# W5500_HR911105A.net
KiCad netlist of a schematic drawn in Altium Designer
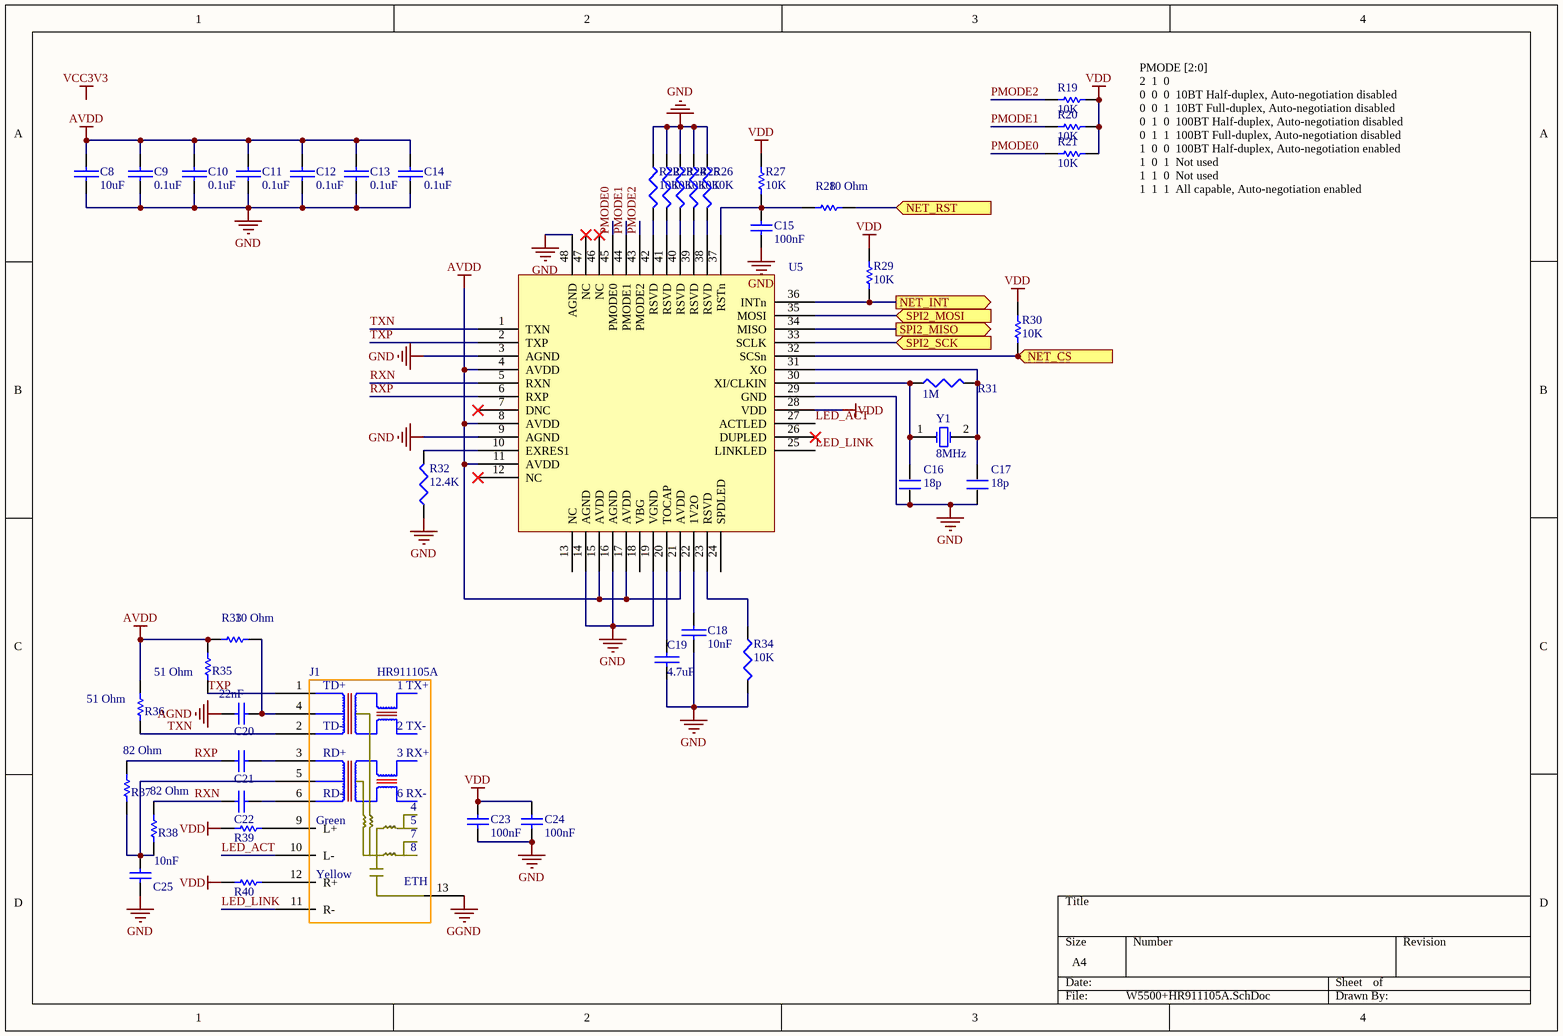
[diagram p0: W5500+HR911105A.SchDoc]

(export (version "E")
  (design (tool "Eeschema 10.0.6"))
  (components
    (comp (ref "C8")
      (value "10uF")
      (footprint "0805")
      (description "0.1uF")
      (libsource (lib "INSPUR_SCH") (part "CAP"))
    )
    (comp (ref "C9") (value "0.1uF") (footprint "0603") (libsource (lib "INSPUR_SCH") (part "CAP")))
    (comp (ref "C10") (value "0.1uF") (footprint "0603") (libsource (lib "INSPUR_SCH") (part "CAP")))
    (comp (ref "C11") (value "0.1uF") (footprint "0603") (libsource (lib "INSPUR_SCH") (part "CAP")))
    (comp (ref "C12") (value "0.1uF") (footprint "0603") (libsource (lib "INSPUR_SCH") (part "CAP")))
    (comp (ref "C13") (value "0.1uF") (footprint "0603") (libsource (lib "INSPUR_SCH") (part "CAP")))
    (comp (ref "C14") (value "0.1uF") (footprint "0603") (libsource (lib "INSPUR_SCH") (part "CAP")))
    (comp (ref "C15")
      (value "100nF")
      (footprint "CAPC0805(2012)145_N")
      (description "CAP 100nF 50V ±5% 0805 (2012 Metric) Thickness 1.45mm SMD")
      (fields (field (name "TOLERANCE") "±5%") (field (name "Comment") "CAP 100nF 50V 0805(2012)"))
      (libsource (lib "Altium Content Vault") (part "CMP-1036-04417-1"))
    )
    (comp (ref "C16") (value "18p") (footprint "0603") (libsource (lib "mylib") (part "C")))
    (comp (ref "C17") (value "18p") (footprint "0603") (libsource (lib "mylib") (part "C")))
    (comp (ref "C18") (value "10nF") (footprint "0603") (libsource (lib "INSPUR_SCH") (part "CAP")))
    (comp (ref "C19")
      (value "4.7uF")
      (footprint "0603")
      (description "0.1uF")
      (libsource (lib "INSPUR_SCH") (part "CAP"))
    )
    (comp (ref "C20")
      (value "22nF")
      (footprint "CAPC0805(2012)130_N")
      (description "CAP 22nF 50V ±5% 0805 (2012 Metric) Thickness 1.2mm SMD")
      (fields (field (name "TOLERANCE") "±5%") (field (name "Comment") "CAP 22nF 50V 0805(2012)"))
      (libsource (lib "Altium Content Vault") (part "CMP-1036-04061-1"))
    )
    (comp (ref "C21")
      (value "CAP 6.8nF 50V 0805(2012)")
      (footprint "CAPC0805(2012)100_L")
      (description "CAP 6.8nF 50V ±1% 0805 (2012 Metric) Thickness 1mm SMD")
      (fields (field (name "TOLERANCE") "±1%"))
      (libsource (lib "Altium Content Vault") (part "CAP"))
    )
    (comp (ref "C22")
      (value "CAP 6.8nF 50V 0805(2012)")
      (footprint "CAPC0805(2012)100_L")
      (description "CAP 6.8nF 50V ±1% 0805 (2012 Metric) Thickness 1mm SMD")
      (fields (field (name "TOLERANCE") "±1%"))
      (libsource (lib "Altium Content Vault") (part "CAP"))
    )
    (comp (ref "C23")
      (value "100nF")
      (footprint "CAPC0805(2012)100_L")
      (description "CAP 100nF 50V ±5% 0805 (2012 Metric) Thickness 1mm SMD")
      (fields (field (name "TOLERANCE") "±5%") (field (name "Comment") "CAP 100nF 50V 0805(2012)"))
      (libsource (lib "Altium Content Vault") (part "CMP-1036-04418-1"))
    )
    (comp (ref "C24")
      (value "100nF")
      (footprint "CAPC0805(2012)100_L")
      (description "CAP 100nF 50V ±5% 0805 (2012 Metric) Thickness 1mm SMD")
      (fields (field (name "TOLERANCE") "±5%") (field (name "Comment") "CAP 100nF 50V 0805(2012)"))
      (libsource (lib "Altium Content Vault") (part "CMP-1036-04418-1"))
    )
    (comp (ref "C25")
      (value "10nF")
      (footprint "CAPC0805(2012)100_M")
      (description "CAP 10nF 50V ±1% 0805 (2012 Metric) Thickness 1mm SMD")
      (fields (field (name "TOLERANCE") "±1%") (field (name "Comment") "CAP 10nF 50V 0805(2012)"))
      (libsource (lib "Altium Content Vault") (part "CMP-1036-03837-1"))
    )
    (comp (ref "J1") (value "HR911105A") (footprint "HR911102") (libsource (lib "*") (part "HR911102")))
    (comp (ref "R19")
      (value "10K")
      (footprint "RESC0805(2012)_M")
      (description "10K 0.125W 1% 0805 (2012 Metric)  SMD")
      (fields (field (name "TOLERANCE") "1 %") (field (name "POWER") "0.125 W"))
      (libsource (lib "Altium Content Vault") (part "CMP-1013-00623-1"))
    )
    (comp (ref "R20")
      (value "10K")
      (footprint "RESC0805(2012)_M")
      (description "10K 0.125W 1% 0805 (2012 Metric)  SMD")
      (fields (field (name "TOLERANCE") "1 %") (field (name "POWER") "0.125 W"))
      (libsource (lib "Altium Content Vault") (part "CMP-1013-00623-1"))
    )
    (comp (ref "R21")
      (value "10K")
      (footprint "RESC0805(2012)_M")
      (description "10K 0.125W 1% 0805 (2012 Metric)  SMD")
      (fields (field (name "TOLERANCE") "1 %") (field (name "POWER") "0.125 W"))
      (libsource (lib "Altium Content Vault") (part "CMP-1013-00623-1"))
    )
    (comp (ref "R22") (value "10K") (footprint "0603") (libsource (lib "INSPUR_SCH") (part "RES1")))
    (comp (ref "R23") (value "10K") (footprint "0603") (libsource (lib "INSPUR_SCH") (part "RES1")))
    (comp (ref "R24") (value "10K") (footprint "0603") (libsource (lib "INSPUR_SCH") (part "RES1")))
    (comp (ref "R25") (value "10K") (footprint "0603") (libsource (lib "INSPUR_SCH") (part "RES1")))
    (comp (ref "R26") (value "10K") (footprint "0603") (libsource (lib "INSPUR_SCH") (part "RES1")))
    (comp (ref "R27")
      (value "10K")
      (footprint "RESC0805(2012)_M")
      (description "10K 0.125W 1% 0805 (2012 Metric)  SMD")
      (fields (field (name "TOLERANCE") "1 %") (field (name "POWER") "0.125 W"))
      (libsource (lib "Altium Content Vault") (part "CMP-1013-00623-1"))
    )
    (comp (ref "R28")
      (value "10 Ohm")
      (footprint "RESC0805(2012)_L")
      (description "10R 0.125W 5% 0805 (2012 Metric)  SMD")
      (fields (field (name "POWER") "0.125 W") (field (name "TOLERANCE") "5 %"))
      (libsource (lib "Altium Content Vault") (part "CMP-1013-00026-1"))
    )
    (comp (ref "R29")
      (value "10K")
      (footprint "RESC0805(2012)_M")
      (description "10K 0.125W 1% 0805 (2012 Metric)  SMD")
      (fields (field (name "TOLERANCE") "1 %") (field (name "POWER") "0.125 W"))
      (libsource (lib "Altium Content Vault") (part "CMP-1013-00623-1"))
    )
    (comp (ref "R30")
      (value "10K")
      (footprint "RESC0805(2012)_M")
      (description "10K 0.125W 1% 0805 (2012 Metric)  SMD")
      (fields (field (name "TOLERANCE") "1 %") (field (name "POWER") "0.125 W"))
      (libsource (lib "Altium Content Vault") (part "CMP-1013-00623-1"))
    )
    (comp (ref "R31") (value "1M") (footprint "0603") (libsource (lib "INSPUR_SCH") (part "RES1")))
    (comp (ref "R32") (value "12.4K") (footprint "0603") (libsource (lib "INSPUR_SCH") (part "RES1")))
    (comp (ref "R33")
      (value "10 Ohm")
      (footprint "RESC0805(2012)_L")
      (description "10R 0.125W 5% 0805 (2012 Metric)  SMD")
      (fields (field (name "POWER") "0.125 W") (field (name "TOLERANCE") "5 %"))
      (libsource (lib "Altium Content Vault") (part "CMP-1013-00026-1"))
    )
    (comp (ref "R34") (value "10K") (footprint "0603") (libsource (lib "INSPUR_SCH") (part "RES1")))
    (comp (ref "R35")
      (value "51 Ohm")
      (footprint "RESC0805(2012)_N")
      (description "51R 0.125W 5% 0805 (2012 Metric)  SMD")
      (fields (field (name "TOLERANCE") "5 %") (field (name "POWER") "0.125 W"))
      (libsource (lib "Altium Content Vault") (part "CMP-1013-00043-1"))
    )
    (comp (ref "R36")
      (value "51 Ohm")
      (footprint "RESC0805(2012)_N")
      (description "51R 0.125W 5% 0805 (2012 Metric)  SMD")
      (fields (field (name "TOLERANCE") "5 %") (field (name "POWER") "0.125 W"))
      (libsource (lib "Altium Content Vault") (part "CMP-1013-00043-1"))
    )
    (comp (ref "R37")
      (value "82 Ohm")
      (footprint "RESC0805(2012)_L")
      (description "82R 0.125W 5% 0805 (2012 Metric)  SMD")
      (fields (field (name "POWER") "0.125 W") (field (name "TOLERANCE") "5 %"))
      (libsource (lib "Altium Content Vault") (part "CMP-1013-00048-1"))
    )
    (comp (ref "R38")
      (value "82 Ohm")
      (footprint "RESC0805(2012)_L")
      (description "82R 0.125W 5% 0805 (2012 Metric)  SMD")
      (fields (field (name "POWER") "0.125 W") (field (name "TOLERANCE") "5 %"))
      (libsource (lib "Altium Content Vault") (part "CMP-1013-00048-1"))
    )
    (comp (ref "R39")
      (value "270R 5% 0805(2012)")
      (footprint "RESC0805(2012)_N")
      (description "270R 0.125W 5% 0805 (2012 Metric)  SMD")
      (fields (field (name "POWER") "0.125 W") (field (name "TOLERANCE") "5 %"))
      (libsource (lib "Altium Content Vault") (part "RES"))
    )
    (comp (ref "R40")
      (value "270R 5% 0805(2012)")
      (footprint "RESC0805(2012)_N")
      (description "270R 0.125W 5% 0805 (2012 Metric)  SMD")
      (fields (field (name "POWER") "0.125 W") (field (name "TOLERANCE") "5 %"))
      (libsource (lib "Altium Content Vault") (part "RES"))
    )
    (comp (ref "U5")
      (value "W5500")
      (footprint "LQFP48_N")
      (description "以太网")
      (libsource (lib "mylib") (part "W5500"))
    )
    (comp (ref "Y1")
      (value "8MHz")
      (footprint "XTAL_US")
      (description "Crystal Oscillator")
      (fields (field (name "PUBLISHER") "Altium Limited"))
      (libsource (lib "mylib") (part "XTAL"))
    )
  )
  (nets
    (net (code "1") (name "/LED_ACT") (class "Default")
      (node (ref "J1") (pin "10") (pinfunction "L-_10") (pintype "passive"))
      (node (ref "U5") (pin "27") (pinfunction "ACTLED_27") (pintype "passive"))
    )
    (net (code "2") (name "/LED_LINK") (class "Default")
      (node (ref "J1") (pin "11") (pinfunction "R-_11") (pintype "passive"))
      (node (ref "U5") (pin "25") (pinfunction "LINKLED_25") (pintype "passive"))
    )
    (net (code "3") (name "/NET_CS") (class "Default")
      (node (ref "R30") (pin "2") (pinfunction "2_2") (pintype "passive"))
      (node (ref "U5") (pin "32") (pinfunction "SCSn_32") (pintype "passive"))
    )
    (net (code "4") (name "/NET_INT") (class "Default")
      (node (ref "R29") (pin "2") (pinfunction "2_2") (pintype "passive"))
      (node (ref "U5") (pin "36") (pinfunction "INTn_36") (pintype "passive"))
    )
    (net (code "5") (name "/NET_RST") (class "Default")
      (node (ref "R28") (pin "1") (pinfunction "1_1") (pintype "passive"))
    )
    (net (code "6") (name "/PMODE0") (class "Default")
      (node (ref "R21") (pin "2") (pinfunction "2_2") (pintype "passive"))
      (node (ref "U5") (pin "45") (pinfunction "PMODE0_45") (pintype "passive"))
    )
    (net (code "7") (name "/PMODE1") (class "Default")
      (node (ref "R20") (pin "2") (pinfunction "2_2") (pintype "passive"))
      (node (ref "U5") (pin "44") (pinfunction "PMODE1_44") (pintype "passive"))
    )
    (net (code "8") (name "/PMODE2") (class "Default")
      (node (ref "R19") (pin "2") (pinfunction "2_2") (pintype "passive"))
      (node (ref "U5") (pin "43") (pinfunction "PMODE2_43") (pintype "passive"))
    )
    (net (code "9") (name "/RXN") (class "Default")
      (node (ref "C22") (pin "1") (pinfunction "1_1") (pintype "passive"))
      (node (ref "R38") (pin "2") (pinfunction "2_2") (pintype "passive"))
      (node (ref "U5") (pin "5") (pinfunction "RXN_5") (pintype "passive"))
    )
    (net (code "10") (name "/RXP") (class "Default")
      (node (ref "C21") (pin "1") (pinfunction "1_1") (pintype "passive"))
      (node (ref "R37") (pin "2") (pinfunction "2_2") (pintype "passive"))
      (node (ref "U5") (pin "6") (pinfunction "RXP_6") (pintype "passive"))
    )
    (net (code "11") (name "/SPI2_MISO") (class "Default")
      (node (ref "U5") (pin "34") (pinfunction "MISO_34") (pintype "passive"))
    )
    (net (code "12") (name "/SPI2_MOSI") (class "Default")
      (node (ref "U5") (pin "35") (pinfunction "MOSI_35") (pintype "passive"))
    )
    (net (code "13") (name "/SPI2_SCK") (class "Default")
      (node (ref "U5") (pin "33") (pinfunction "SCLK_33") (pintype "passive"))
    )
    (net (code "14") (name "/TXN") (class "Default")
      (node (ref "J1") (pin "2") (pintype "passive"))
      (node (ref "R36") (pin "1") (pinfunction "1_1") (pintype "passive"))
      (node (ref "U5") (pin "1") (pinfunction "TXN_1") (pintype "passive"))
    )
    (net (code "15") (name "/TXP") (class "Default")
      (node (ref "J1") (pin "1") (pintype "passive"))
      (node (ref "R35") (pin "1") (pinfunction "1_1") (pintype "passive"))
      (node (ref "U5") (pin "2") (pinfunction "TXP_2") (pintype "passive"))
    )
    (net (code "16") (name "AGND") (class "Default")
      (node (ref "C20") (pin "1") (pinfunction "1_1") (pintype "passive"))
    )
    (net (code "17") (name "AVDD") (class "Default")
      (node (ref "C10") (pin "1") (pinfunction "1_1") (pintype "passive"))
      (node (ref "C11") (pin "1") (pinfunction "1_1") (pintype "passive"))
      (node (ref "C12") (pin "1") (pinfunction "1_1") (pintype "passive"))
      (node (ref "C13") (pin "1") (pinfunction "1_1") (pintype "passive"))
      (node (ref "C14") (pin "1") (pinfunction "1_1") (pintype "passive"))
      (node (ref "C8") (pin "2") (pinfunction "2_2") (pintype "passive"))
      (node (ref "C9") (pin "1") (pinfunction "1_1") (pintype "passive"))
      (node (ref "R33") (pin "2") (pinfunction "2_2") (pintype "passive"))
      (node (ref "R35") (pin "2") (pinfunction "2_2") (pintype "passive"))
      (node (ref "R36") (pin "2") (pinfunction "2_2") (pintype "passive"))
      (node (ref "U5") (pin "11") (pinfunction "AVDD_11") (pintype "passive"))
      (node (ref "U5") (pin "15") (pinfunction "AVDD_15") (pintype "passive"))
      (node (ref "U5") (pin "17") (pinfunction "AVDD_17") (pintype "passive"))
      (node (ref "U5") (pin "21") (pinfunction "AVDD_21") (pintype "passive"))
      (node (ref "U5") (pin "4") (pinfunction "AVDD_4") (pintype "passive"))
      (node (ref "U5") (pin "8") (pinfunction "AVDD_8") (pintype "passive"))
    )
    (net (code "18") (name "GGND") (class "Default") (node (ref "J1") (pin "13") (pintype "passive")))
    (net (code "19") (name "GND") (class "Default")
      (node (ref "C10") (pin "2") (pinfunction "2_2") (pintype "passive"))
      (node (ref "C11") (pin "2") (pinfunction "2_2") (pintype "passive"))
      (node (ref "C12") (pin "2") (pinfunction "2_2") (pintype "passive"))
      (node (ref "C13") (pin "2") (pinfunction "2_2") (pintype "passive"))
      (node (ref "C14") (pin "2") (pinfunction "2_2") (pintype "passive"))
      (node (ref "C15") (pin "1") (pinfunction "1_1") (pintype "passive"))
      (node (ref "C16") (pin "1") (pintype "passive"))
      (node (ref "C17") (pin "1") (pintype "passive"))
      (node (ref "C18") (pin "2") (pinfunction "2_2") (pintype "passive"))
      (node (ref "C19") (pin "1") (pinfunction "1_1") (pintype "passive"))
      (node (ref "C23") (pin "1") (pinfunction "1_1") (pintype "passive"))
      (node (ref "C24") (pin "1") (pinfunction "1_1") (pintype "passive"))
      (node (ref "C25") (pin "1") (pinfunction "1_1") (pintype "passive"))
      (node (ref "C8") (pin "1") (pinfunction "1_1") (pintype "passive"))
      (node (ref "C9") (pin "2") (pinfunction "2_2") (pintype "passive"))
      (node (ref "R22") (pin "1") (pinfunction "1_1") (pintype "passive"))
      (node (ref "R23") (pin "1") (pinfunction "1_1") (pintype "passive"))
      (node (ref "R24") (pin "1") (pinfunction "1_1") (pintype "passive"))
      (node (ref "R25") (pin "1") (pinfunction "1_1") (pintype "passive"))
      (node (ref "R26") (pin "1") (pinfunction "1_1") (pintype "passive"))
      (node (ref "R32") (pin "1") (pinfunction "1_1") (pintype "passive"))
      (node (ref "R34") (pin "2") (pinfunction "2_2") (pintype "passive"))
      (node (ref "U5") (pin "14") (pinfunction "AGND_14") (pintype "passive"))
      (node (ref "U5") (pin "16") (pinfunction "AGND_16") (pintype "passive"))
      (node (ref "U5") (pin "19") (pinfunction "VGND_19") (pintype "passive"))
      (node (ref "U5") (pin "29") (pinfunction "GND_29") (pintype "passive"))
      (node (ref "U5") (pin "3") (pinfunction "AGND_3") (pintype "passive"))
      (node (ref "U5") (pin "48") (pinfunction "AGND_48") (pintype "passive"))
      (node (ref "U5") (pin "9") (pinfunction "AGND_9") (pintype "passive"))
    )
    (net (code "20") (name "Net-(C20-Pad2)") (class "Default")
      (node (ref "C20") (pin "2") (pinfunction "2_2") (pintype "passive"))
      (node (ref "J1") (pin "4") (pintype "passive"))
      (node (ref "R33") (pin "1") (pinfunction "1_1") (pintype "passive"))
    )
    (net (code "21") (name "Net-(C21-Pad2)") (class "Default")
      (node (ref "C21") (pin "2") (pinfunction "2_2") (pintype "passive"))
      (node (ref "J1") (pin "3") (pintype "passive"))
    )
    (net (code "22") (name "Net-(C22-Pad2)") (class "Default")
      (node (ref "C22") (pin "2") (pinfunction "2_2") (pintype "passive"))
      (node (ref "J1") (pin "6") (pintype "passive"))
    )
    (net (code "23") (name "Net-(C25-Pad2)") (class "Default")
      (node (ref "C25") (pin "2") (pinfunction "2_2") (pintype "passive"))
      (node (ref "J1") (pin "5") (pintype "passive"))
      (node (ref "R37") (pin "1") (pinfunction "1_1") (pintype "passive"))
      (node (ref "R38") (pin "1") (pinfunction "1_1") (pintype "passive"))
    )
    (net (code "24") (name "Net-(J1-L+)") (class "Default")
      (node (ref "J1") (pin "9") (pinfunction "L+_9") (pintype "passive"))
      (node (ref "R39") (pin "2") (pinfunction "2_2") (pintype "passive"))
    )
    (net (code "25") (name "Net-(J1-R+)") (class "Default")
      (node (ref "J1") (pin "12") (pinfunction "R+_12") (pintype "passive"))
      (node (ref "R40") (pin "2") (pinfunction "2_2") (pintype "passive"))
    )
    (net (code "26") (name "Net-(R22-Pad2)") (class "Default")
      (node (ref "R22") (pin "2") (pinfunction "2_2") (pintype "passive"))
      (node (ref "U5") (pin "42") (pinfunction "RSVD_42") (pintype "passive"))
    )
    (net (code "27") (name "Net-(R23-Pad2)") (class "Default")
      (node (ref "R23") (pin "2") (pinfunction "2_2") (pintype "passive"))
      (node (ref "U5") (pin "41") (pinfunction "RSVD_41") (pintype "passive"))
    )
    (net (code "28") (name "Net-(R24-Pad2)") (class "Default")
      (node (ref "R24") (pin "2") (pinfunction "2_2") (pintype "passive"))
      (node (ref "U5") (pin "40") (pinfunction "RSVD_40") (pintype "passive"))
    )
    (net (code "29") (name "Net-(R25-Pad2)") (class "Default")
      (node (ref "R25") (pin "2") (pinfunction "2_2") (pintype "passive"))
      (node (ref "U5") (pin "39") (pinfunction "RSVD_39") (pintype "passive"))
    )
    (net (code "30") (name "Net-(R26-Pad2)") (class "Default")
      (node (ref "R26") (pin "2") (pinfunction "2_2") (pintype "passive"))
      (node (ref "U5") (pin "38") (pinfunction "RSVD_38") (pintype "passive"))
    )
    (net (code "31") (name "Net-(R34-Pad1)") (class "Default")
      (node (ref "R34") (pin "1") (pinfunction "1_1") (pintype "passive"))
      (node (ref "U5") (pin "23") (pinfunction "RSVD_23") (pintype "passive"))
    )
    (net (code "32") (name "Net-(U5-1V2O)") (class "Default")
      (node (ref "C18") (pin "1") (pinfunction "1_1") (pintype "passive"))
      (node (ref "U5") (pin "22") (pinfunction "1V2O_22") (pintype "passive"))
    )
    (net (code "33") (name "Net-(U5-EXRES1)") (class "Default")
      (node (ref "R32") (pin "2") (pinfunction "2_2") (pintype "passive"))
      (node (ref "U5") (pin "10") (pinfunction "EXRES1_10") (pintype "passive"))
    )
    (net (code "34") (name "Net-(U5-RSTn)") (class "Default")
      (node (ref "C15") (pin "2") (pinfunction "2_2") (pintype "passive"))
      (node (ref "R27") (pin "2") (pinfunction "2_2") (pintype "passive"))
      (node (ref "R28") (pin "2") (pinfunction "2_2") (pintype "passive"))
      (node (ref "U5") (pin "37") (pinfunction "RSTn_37") (pintype "passive"))
    )
    (net (code "35") (name "Net-(U5-TOCAP)") (class "Default")
      (node (ref "C19") (pin "2") (pinfunction "2_2") (pintype "passive"))
      (node (ref "U5") (pin "20") (pinfunction "TOCAP_20") (pintype "passive"))
    )
    (net (code "36") (name "Net-(U5-XI{slash}CLKIN)") (class "Default")
      (node (ref "C16") (pin "2") (pintype "passive"))
      (node (ref "R31") (pin "1") (pinfunction "1_1") (pintype "passive"))
      (node (ref "U5") (pin "30") (pinfunction "XI/CLKIN_30") (pintype "passive"))
      (node (ref "Y1") (pin "1") (pinfunction "OSC1_1") (pintype "passive"))
    )
    (net (code "37") (name "Net-(U5-XO)") (class "Default")
      (node (ref "C17") (pin "2") (pintype "passive"))
      (node (ref "R31") (pin "2") (pinfunction "2_2") (pintype "passive"))
      (node (ref "U5") (pin "31") (pinfunction "XO_31") (pintype "passive"))
      (node (ref "Y1") (pin "2") (pinfunction "OSC2_2") (pintype "passive"))
    )
    (net (code "39") (name "VDD") (class "Default")
      (node (ref "C23") (pin "2") (pinfunction "2_2") (pintype "passive"))
      (node (ref "C24") (pin "2") (pinfunction "2_2") (pintype "passive"))
      (node (ref "R19") (pin "1") (pinfunction "1_1") (pintype "passive"))
      (node (ref "R20") (pin "1") (pinfunction "1_1") (pintype "passive"))
      (node (ref "R21") (pin "1") (pinfunction "1_1") (pintype "passive"))
      (node (ref "R27") (pin "1") (pinfunction "1_1") (pintype "passive"))
      (node (ref "R29") (pin "1") (pinfunction "1_1") (pintype "passive"))
      (node (ref "R30") (pin "1") (pinfunction "1_1") (pintype "passive"))
      (node (ref "R39") (pin "1") (pinfunction "1_1") (pintype "passive"))
      (node (ref "R40") (pin "1") (pinfunction "1_1") (pintype "passive"))
      (node (ref "U5") (pin "28") (pinfunction "VDD_28") (pintype "passive"))
    )
    (net (code "40") (name "unconnected-(U5-DNC-Pad7)") (class "Default")
      (node (ref "U5") (pin "7") (pinfunction "DNC_7") (pintype "passive+no_connect"))
    )
    (net (code "41") (name "unconnected-(U5-DUPLED-Pad26)") (class "Default")
      (node (ref "U5") (pin "26") (pinfunction "DUPLED_26") (pintype "passive+no_connect"))
    )
    (net (code "42") (name "unconnected-(U5-NC-Pad12)") (class "Default")
      (node (ref "U5") (pin "12") (pinfunction "NC_12") (pintype "passive+no_connect"))
    )
    (net (code "43") (name "unconnected-(U5-NC-Pad13)") (class "Default")
      (node (ref "U5") (pin "13") (pinfunction "NC_13") (pintype "passive"))
    )
    (net (code "44") (name "unconnected-(U5-NC-Pad46)") (class "Default")
      (node (ref "U5") (pin "46") (pinfunction "NC_46") (pintype "passive+no_connect"))
    )
    (net (code "45") (name "unconnected-(U5-NC-Pad47)") (class "Default")
      (node (ref "U5") (pin "47") (pinfunction "NC_47") (pintype "passive+no_connect"))
    )
    (net (code "46") (name "unconnected-(U5-SPDLED-Pad24)") (class "Default")
      (node (ref "U5") (pin "24") (pinfunction "SPDLED_24") (pintype "passive"))
    )
    (net (code "47") (name "unconnected-(U5-VBG-Pad18)") (class "Default")
      (node (ref "U5") (pin "18") (pinfunction "VBG_18") (pintype "passive"))
    )
  )
)
